# SG_circuit.net
KiCad netlist of a schematic drawn in EAGLE
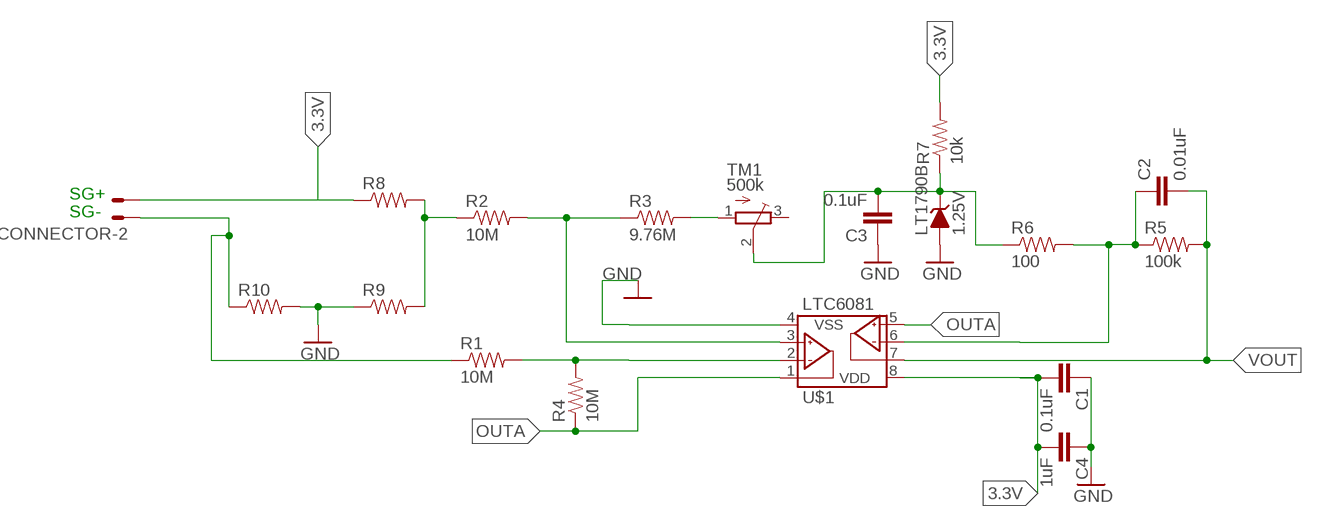
[diagram p0: schematic, sheet 1]

(export (version "E")
  (design (tool "Eeschema 10.0.6"))
  (components
    (comp (ref "C1")
      (value "0.1uF")
      (footprint "eagle-import:0805")
      (libsource (lib "eagle-import") (part "CAP0805"))
    )
    (comp (ref "C2")
      (value "0.01uF")
      (footprint "eagle-import:0805")
      (libsource (lib "eagle-import") (part "CAP0805"))
    )
    (comp (ref "C3")
      (value "0.1uF")
      (footprint "eagle-import:0805")
      (libsource (lib "eagle-import") (part "CAP0805"))
    )
    (comp (ref "C4")
      (value "1uF")
      (footprint "eagle-import:0805")
      (libsource (lib "eagle-import") (part "CAP0805"))
    )
    (comp (ref "LT1790B")
      (value "1.25V")
      (footprint "eagle-import:0805_D")
      (libsource (lib "eagle-import") (part "DIODE_ZENER0805"))
    )
    (comp (ref "R1")
      (value "10M")
      (footprint "eagle-import:0805")
      (libsource (lib "eagle-import") (part "RESISTOR0805-RES"))
    )
    (comp (ref "R2")
      (value "10M")
      (footprint "eagle-import:0805")
      (libsource (lib "eagle-import") (part "RESISTOR0805-RES"))
    )
    (comp (ref "R3")
      (value "9.76M")
      (footprint "eagle-import:0805")
      (libsource (lib "eagle-import") (part "RESISTOR0805-RES"))
    )
    (comp (ref "R4")
      (value "10M")
      (footprint "eagle-import:0805")
      (libsource (lib "eagle-import") (part "RESISTOR0805-RES"))
    )
    (comp (ref "R5")
      (value "100k")
      (footprint "eagle-import:0805")
      (libsource (lib "eagle-import") (part "RESISTOR0805-RES"))
    )
    (comp (ref "R6")
      (value "100")
      (footprint "eagle-import:0805")
      (libsource (lib "eagle-import") (part "RESISTOR0805-RES"))
    )
    (comp (ref "R7")
      (value "10k")
      (footprint "eagle-import:0805")
      (libsource (lib "eagle-import") (part "RESISTOR0805-RES"))
    )
    (comp (ref "R8")
      (value "RESISTOR0805-RES")
      (footprint "eagle-import:0805")
      (libsource (lib "eagle-import") (part "RESISTOR0805-RES"))
    )
    (comp (ref "R9")
      (value "RESISTOR0805-RES")
      (footprint "eagle-import:0805")
      (libsource (lib "eagle-import") (part "RESISTOR0805-RES"))
    )
    (comp (ref "R10")
      (value "RESISTOR0805-RES")
      (footprint "eagle-import:0805")
      (libsource (lib "eagle-import") (part "RESISTOR0805-RES"))
    )
    (comp (ref "SG+")
      (value "CONNECTOR-2")
      (footprint "eagle-import:MINIFIT_5566-2")
      (libsource (lib "eagle-import") (part "CONNECTOR-2"))
    )
    (comp (ref "TM1")
      (value "500k")
      (footprint "eagle-import:TC33X")
      (libsource (lib "eagle-import") (part "TRIMPOTTC33X"))
    )
    (comp (ref "U$1")
      (value "LTC6081")
      (footprint "eagle-import:MSOP-8_MS")
      (libsource (lib "eagle-import") (part "LTC6081"))
    )
  )
  (nets
    (net (code "1") (name "3.3V") (class "Default")
      (node (ref "C1") (pin "2") (pinfunction "2_2") (pintype "passive"))
      (node (ref "C4") (pin "2") (pinfunction "2_2") (pintype "passive"))
      (node (ref "R7") (pin "2") (pinfunction "2_2") (pintype "passive"))
      (node (ref "R8") (pin "1") (pinfunction "1_1") (pintype "passive"))
      (node (ref "SG+") (pin "2") (pinfunction "S_2") (pintype "passive"))
      (node (ref "U$1") (pin "8") (pinfunction "VDD_8") (pintype "passive"))
    )
    (net (code "2") (name "GND") (class "Default")
      (node (ref "C1") (pin "1") (pinfunction "1_1") (pintype "passive"))
      (node (ref "C3") (pin "1") (pinfunction "1_1") (pintype "passive"))
      (node (ref "C4") (pin "1") (pinfunction "1_1") (pintype "passive"))
      (node (ref "LT1790B") (pin "A") (pinfunction "A_A") (pintype "passive"))
      (node (ref "R10") (pin "2") (pinfunction "2_2") (pintype "passive"))
      (node (ref "R9") (pin "1") (pinfunction "1_1") (pintype "passive"))
      (node (ref "U$1") (pin "4") (pinfunction "VSS_4") (pintype "passive"))
    )
    (net (code "3") (name "Net-(R2-Pad1)") (class "Default")
      (node (ref "R2") (pin "1") (pinfunction "1_1") (pintype "passive"))
      (node (ref "R8") (pin "2") (pinfunction "2_2") (pintype "passive"))
      (node (ref "R9") (pin "2") (pinfunction "2_2") (pintype "passive"))
    )
    (net (code "4") (name "Net-(SG+A-S)") (class "Default")
      (node (ref "R1") (pin "1") (pinfunction "1_1") (pintype "passive"))
      (node (ref "R10") (pin "1") (pinfunction "1_1") (pintype "passive"))
      (node (ref "SG+") (pin "1") (pinfunction "S_1") (pintype "passive"))
    )
    (net (code "5") (name "Net-(TM1-A)") (class "Default")
      (node (ref "R3") (pin "2") (pinfunction "2_2") (pintype "passive"))
      (node (ref "TM1") (pin "1") (pinfunction "A_1") (pintype "passive"))
    )
    (net (code "6") (name "Net-(TM1-S)") (class "Default")
      (node (ref "C3") (pin "2") (pinfunction "2_2") (pintype "passive"))
      (node (ref "LT1790B") (pin "C") (pinfunction "C_C") (pintype "passive"))
      (node (ref "R6") (pin "1") (pinfunction "1_1") (pintype "passive"))
      (node (ref "R7") (pin "1") (pinfunction "1_1") (pintype "passive"))
      (node (ref "TM1") (pin "2") (pinfunction "S_2") (pintype "passive"))
    )
    (net (code "7") (name "Net-(U$1-VINA+)") (class "Default")
      (node (ref "R2") (pin "2") (pinfunction "2_2") (pintype "passive"))
      (node (ref "R3") (pin "1") (pinfunction "1_1") (pintype "passive"))
      (node (ref "U$1") (pin "3") (pinfunction "VINA+_3") (pintype "passive"))
    )
    (net (code "8") (name "Net-(U$1-VINA-)") (class "Default")
      (node (ref "R1") (pin "2") (pinfunction "2_2") (pintype "passive"))
      (node (ref "R4") (pin "2") (pinfunction "2_2") (pintype "passive"))
      (node (ref "U$1") (pin "2") (pinfunction "VINA-_2") (pintype "passive"))
    )
    (net (code "9") (name "Net-(U$1-VINB-)") (class "Default")
      (node (ref "C2") (pin "1") (pinfunction "1_1") (pintype "passive"))
      (node (ref "R5") (pin "1") (pinfunction "1_1") (pintype "passive"))
      (node (ref "R6") (pin "2") (pinfunction "2_2") (pintype "passive"))
      (node (ref "U$1") (pin "6") (pinfunction "VINB-_6") (pintype "passive"))
    )
    (net (code "10") (name "OUTA") (class "Default")
      (node (ref "R4") (pin "1") (pinfunction "1_1") (pintype "passive"))
      (node (ref "U$1") (pin "1") (pinfunction "VOUTA_1") (pintype "passive"))
      (node (ref "U$1") (pin "5") (pinfunction "VINB+_5") (pintype "passive"))
    )
    (net (code "11") (name "VOUT") (class "Default")
      (node (ref "C2") (pin "2") (pinfunction "2_2") (pintype "passive"))
      (node (ref "R5") (pin "2") (pinfunction "2_2") (pintype "passive"))
      (node (ref "U$1") (pin "7") (pinfunction "VOUTB_7") (pintype "passive"))
    )
    (net (code "12") (name "unconnected-(TM1-E-Pad3)") (class "Default")
      (node (ref "TM1") (pin "3") (pinfunction "E_3") (pintype "passive"))
    )
  )
)
